# CPU_BOARD.net
KiCad netlist of a schematic drawn in EAGLE
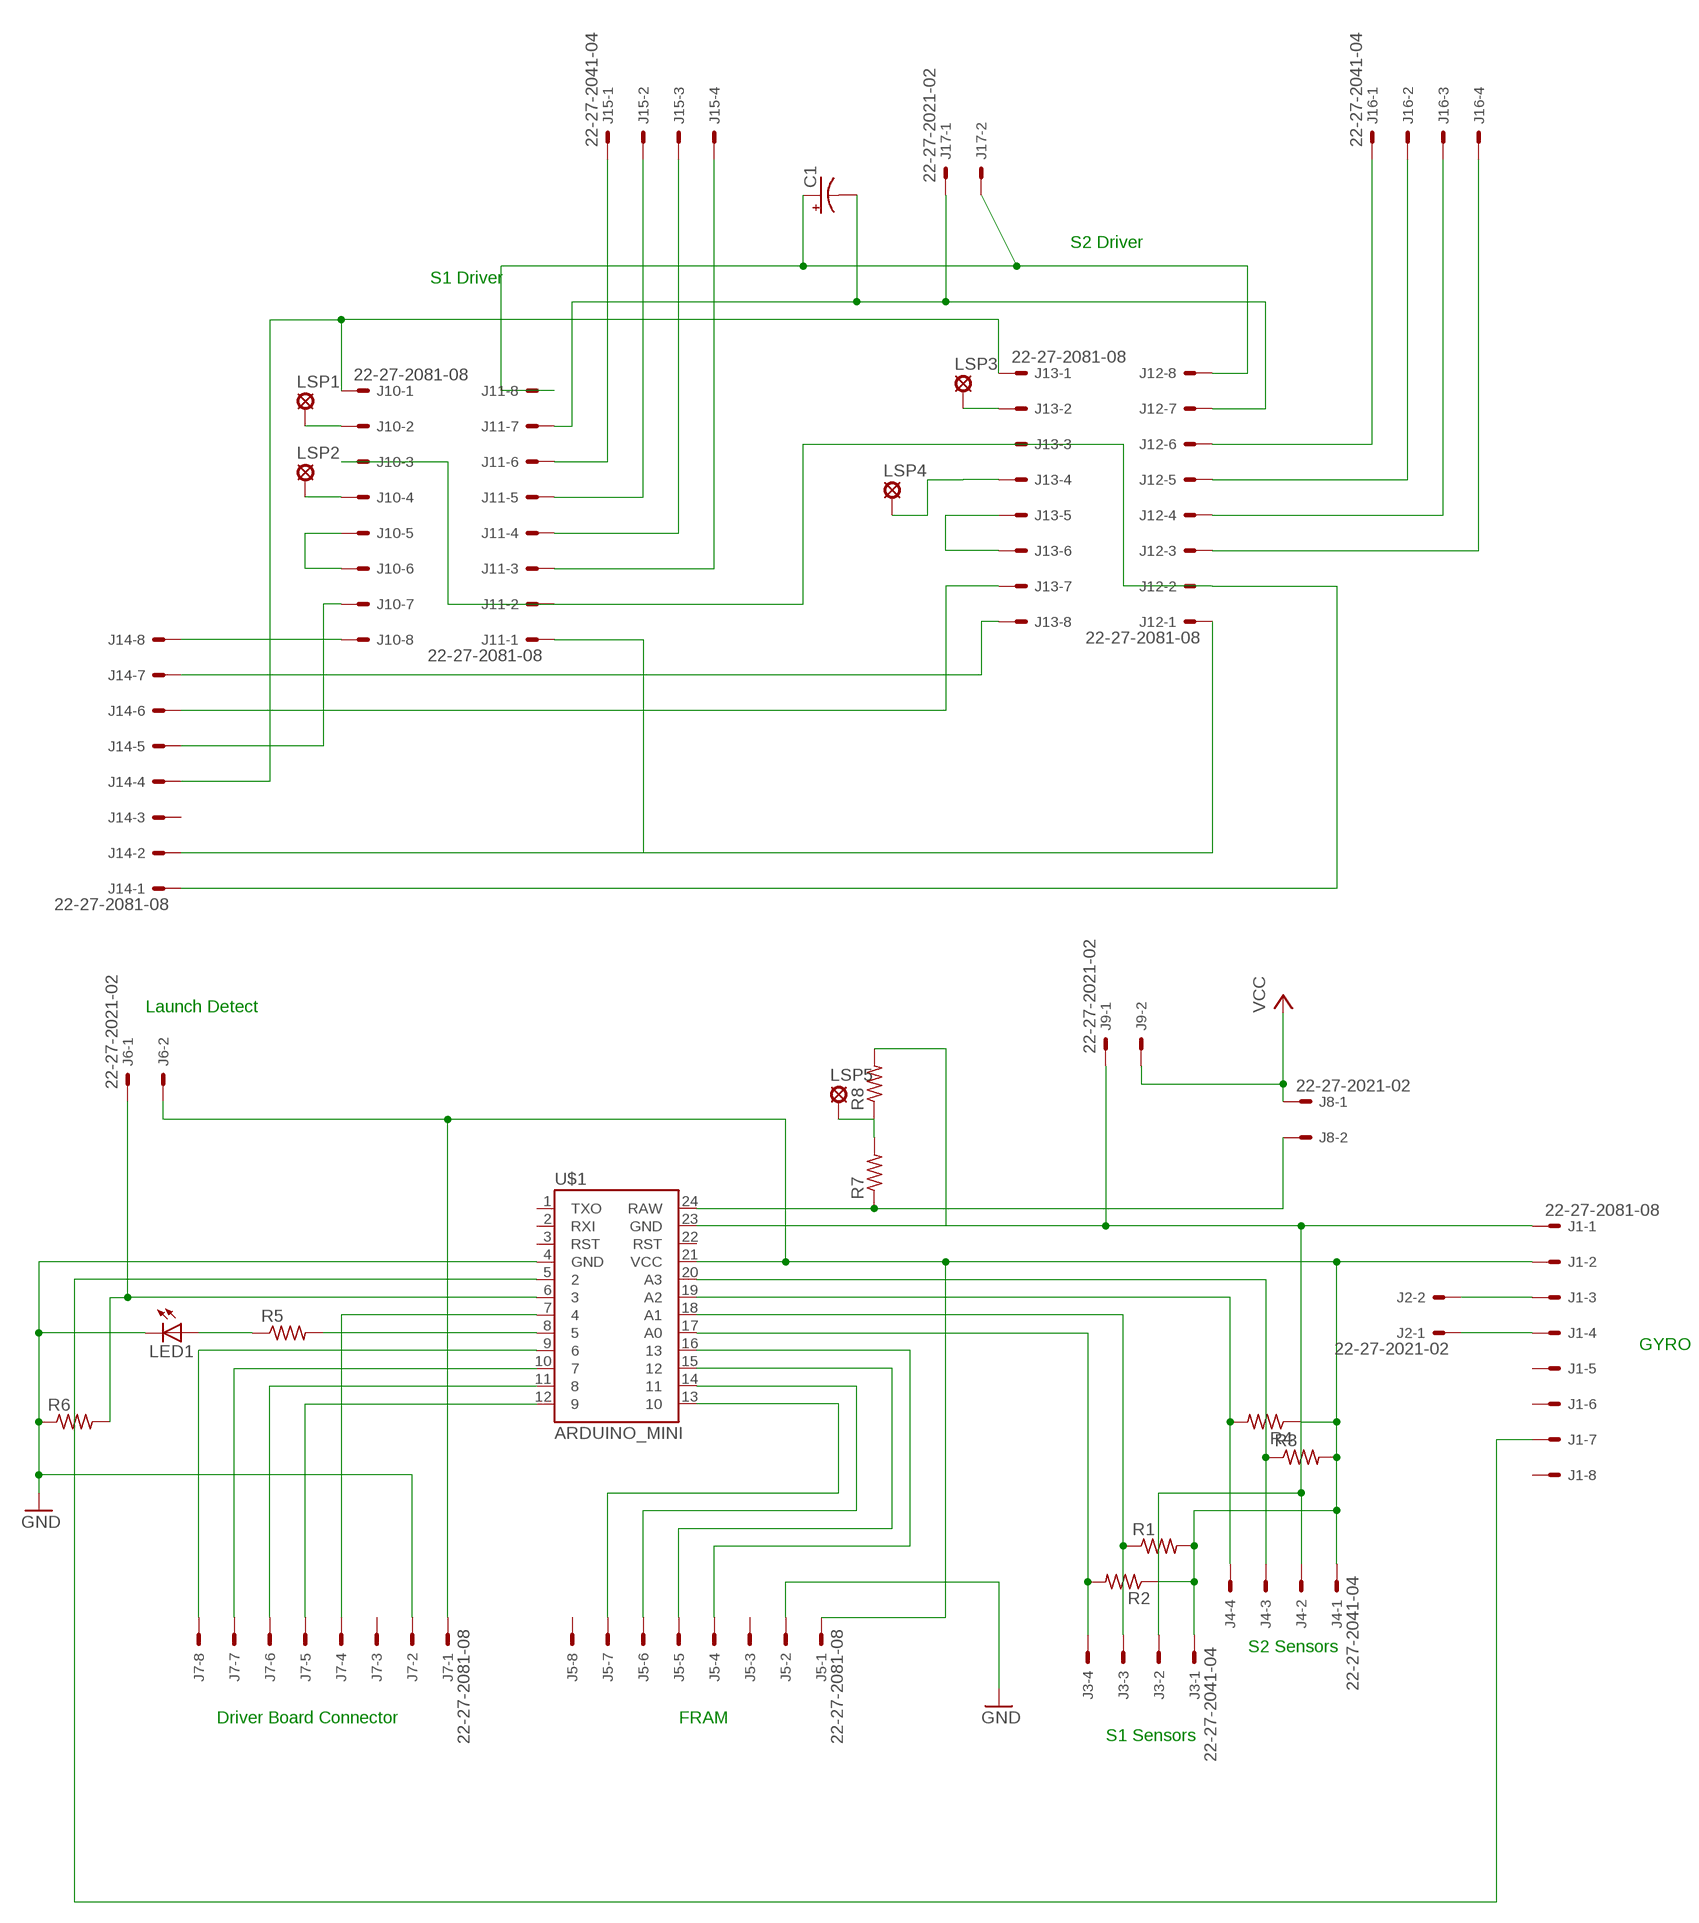
[diagram p0: schematic, sheet 1]

(export (version "E")
  (design (tool "Eeschema 10.0.6"))
  (components
    (comp (ref "C1")
      (value "CPOL-USE2.5-7")
      (footprint "eagle-import:E2,5-7")
      (libsource (lib "eagle-import") (part "CPOL-USE2.5-7"))
    )
    (comp (ref "J1")
      (value "22-27-2081-08")
      (footprint "eagle-import:6410-08")
      (libsource (lib "eagle-import") (part "22-?-0827-2081"))
    )
    (comp (ref "J2")
      (value "22-27-2021-02")
      (footprint "eagle-import:6410-02")
      (libsource (lib "eagle-import") (part "22-?-0227-2021"))
    )
    (comp (ref "J3")
      (value "22-27-2041-04")
      (footprint "eagle-import:6410-04")
      (libsource (lib "eagle-import") (part "22-?-0427-2041"))
    )
    (comp (ref "J4")
      (value "22-27-2041-04")
      (footprint "eagle-import:6410-04")
      (libsource (lib "eagle-import") (part "22-?-0427-2041"))
    )
    (comp (ref "J5")
      (value "22-27-2081-08")
      (footprint "eagle-import:6410-08")
      (libsource (lib "eagle-import") (part "22-?-0827-2081"))
    )
    (comp (ref "J6")
      (value "22-27-2021-02")
      (footprint "eagle-import:6410-02")
      (libsource (lib "eagle-import") (part "22-?-0227-2021"))
    )
    (comp (ref "J7")
      (value "22-27-2081-08")
      (footprint "eagle-import:6410-08")
      (libsource (lib "eagle-import") (part "22-?-0827-2081"))
    )
    (comp (ref "J8")
      (value "22-27-2021-02")
      (footprint "eagle-import:6410-02")
      (libsource (lib "eagle-import") (part "22-?-0227-2021"))
    )
    (comp (ref "J9")
      (value "22-27-2021-02")
      (footprint "eagle-import:6410-02")
      (libsource (lib "eagle-import") (part "22-?-0227-2021"))
    )
    (comp (ref "J10")
      (value "22-27-2081-08")
      (footprint "eagle-import:6410-08")
      (libsource (lib "eagle-import") (part "22-?-0827-2081"))
    )
    (comp (ref "J11")
      (value "22-27-2081-08")
      (footprint "eagle-import:6410-08")
      (libsource (lib "eagle-import") (part "22-?-0827-2081"))
    )
    (comp (ref "J12")
      (value "22-27-2081-08")
      (footprint "eagle-import:6410-08")
      (libsource (lib "eagle-import") (part "22-?-0827-2081"))
    )
    (comp (ref "J13")
      (value "22-27-2081-08")
      (footprint "eagle-import:6410-08")
      (libsource (lib "eagle-import") (part "22-?-0827-2081"))
    )
    (comp (ref "J14")
      (value "22-27-2081-08")
      (footprint "eagle-import:6410-08")
      (libsource (lib "eagle-import") (part "22-?-0827-2081"))
    )
    (comp (ref "J15")
      (value "22-27-2041-04")
      (footprint "eagle-import:6410-04")
      (libsource (lib "eagle-import") (part "22-?-0427-2041"))
    )
    (comp (ref "J16")
      (value "22-27-2041-04")
      (footprint "eagle-import:6410-04")
      (libsource (lib "eagle-import") (part "22-?-0427-2041"))
    )
    (comp (ref "J17")
      (value "22-27-2021-02")
      (footprint "eagle-import:6410-02")
      (libsource (lib "eagle-import") (part "22-?-0227-2021"))
    )
    (comp (ref "LED1")
      (value "LED5MM")
      (footprint "eagle-import:LED5MM")
      (libsource (lib "eagle-import") (part "LED5MM"))
    )
    (comp (ref "LSP1")
      (value "LSP10")
      (footprint "eagle-import:LSP10")
      (libsource (lib "eagle-import") (part "LSP10"))
    )
    (comp (ref "LSP2")
      (value "LSP10")
      (footprint "eagle-import:LSP10")
      (libsource (lib "eagle-import") (part "LSP10"))
    )
    (comp (ref "LSP3")
      (value "LSP10")
      (footprint "eagle-import:LSP10")
      (libsource (lib "eagle-import") (part "LSP10"))
    )
    (comp (ref "LSP4")
      (value "LSP10")
      (footprint "eagle-import:LSP10")
      (libsource (lib "eagle-import") (part "LSP10"))
    )
    (comp (ref "LSP5")
      (value "LSP11")
      (footprint "eagle-import:LSP11")
      (libsource (lib "eagle-import") (part "LSP11"))
    )
    (comp (ref "R1")
      (value "R-US_0204/5")
      (footprint "eagle-import:0204_5")
      (libsource (lib "eagle-import") (part "R-US_0204/5"))
    )
    (comp (ref "R2")
      (value "R-US_0204/5")
      (footprint "eagle-import:0204_5")
      (libsource (lib "eagle-import") (part "R-US_0204/5"))
    )
    (comp (ref "R3")
      (value "R-US_0204/5")
      (footprint "eagle-import:0204_5")
      (libsource (lib "eagle-import") (part "R-US_0204/5"))
    )
    (comp (ref "R4")
      (value "R-US_0204/5")
      (footprint "eagle-import:0204_5")
      (libsource (lib "eagle-import") (part "R-US_0204/5"))
    )
    (comp (ref "R5")
      (value "R-US_0204/5")
      (footprint "eagle-import:0204_5")
      (libsource (lib "eagle-import") (part "resistor_R-US_0204/5"))
    )
    (comp (ref "R6")
      (value "R-US_0204/5")
      (footprint "eagle-import:0204_5")
      (libsource (lib "eagle-import") (part "R-US_0204/5"))
    )
    (comp (ref "R7")
      (value "R-US_0204/5")
      (footprint "eagle-import:0204_5")
      (libsource (lib "eagle-import") (part "R-US_0204/5"))
    )
    (comp (ref "R8")
      (value "R-US_0204/5")
      (footprint "eagle-import:0204_5")
      (libsource (lib "eagle-import") (part "R-US_0204/5"))
    )
    (comp (ref "U$1")
      (value "ARDUINO_MINI")
      (footprint "eagle-import:ARDUINO_MINI")
      (libsource (lib "eagle-import") (part "ARDUINO_MINI"))
    )
  )
  (nets
    (net (code "1") (name "GND") (class "Default")
      (node (ref "J5") (pin "2") (pinfunction "S_2") (pintype "passive"))
      (node (ref "J7") (pin "2") (pinfunction "S_2") (pintype "passive"))
      (node (ref "LED1") (pin "K") (pinfunction "C_K") (pintype "passive"))
      (node (ref "R6") (pin "1") (pinfunction "1_1") (pintype "passive"))
      (node (ref "U$1") (pin "4") (pinfunction "GND_4") (pintype "bidirectional"))
    )
    (net (code "2") (name "Net-(J1A-S)") (class "Default")
      (node (ref "J1") (pin "1") (pinfunction "S_1") (pintype "passive"))
      (node (ref "J3") (pin "2") (pinfunction "S_2") (pintype "passive"))
      (node (ref "J4") (pin "2") (pinfunction "S_2") (pintype "passive"))
      (node (ref "J9") (pin "1") (pinfunction "S_1") (pintype "passive"))
      (node (ref "R8") (pin "2") (pinfunction "2_2") (pintype "passive"))
      (node (ref "U$1") (pin "23") (pinfunction "GND_23") (pintype "bidirectional"))
    )
    (net (code "3") (name "Net-(J1B-S)") (class "Default")
      (node (ref "J1") (pin "2") (pinfunction "S_2") (pintype "passive"))
      (node (ref "J3") (pin "1") (pinfunction "S_1") (pintype "passive"))
      (node (ref "J4") (pin "1") (pinfunction "S_1") (pintype "passive"))
      (node (ref "J5") (pin "1") (pinfunction "S_1") (pintype "passive"))
      (node (ref "J6") (pin "2") (pinfunction "S_2") (pintype "passive"))
      (node (ref "J7") (pin "1") (pinfunction "S_1") (pintype "passive"))
      (node (ref "R1") (pin "2") (pinfunction "2_2") (pintype "passive"))
      (node (ref "R2") (pin "1") (pinfunction "1_1") (pintype "passive"))
      (node (ref "R3") (pin "2") (pinfunction "2_2") (pintype "passive"))
      (node (ref "R4") (pin "1") (pinfunction "1_1") (pintype "passive"))
      (node (ref "U$1") (pin "21") (pinfunction "VCC_21") (pintype "bidirectional"))
    )
    (net (code "4") (name "Net-(J1C-S)") (class "Default")
      (node (ref "J1") (pin "3") (pinfunction "S_3") (pintype "passive"))
      (node (ref "J2") (pin "2") (pinfunction "S_2") (pintype "passive"))
    )
    (net (code "5") (name "Net-(J1D-S)") (class "Default")
      (node (ref "J1") (pin "4") (pinfunction "S_4") (pintype "passive"))
      (node (ref "J2") (pin "1") (pinfunction "S_1") (pintype "passive"))
    )
    (net (code "6") (name "Net-(J1G-S)") (class "Default")
      (node (ref "J1") (pin "7") (pinfunction "S_7") (pintype "passive"))
      (node (ref "U$1") (pin "5") (pinfunction "2_5") (pintype "bidirectional"))
    )
    (net (code "7") (name "Net-(J3C-S)") (class "Default")
      (node (ref "J3") (pin "3") (pinfunction "S_3") (pintype "passive"))
      (node (ref "R1") (pin "1") (pinfunction "1_1") (pintype "passive"))
      (node (ref "U$1") (pin "18") (pinfunction "A1_18") (pintype "bidirectional"))
    )
    (net (code "8") (name "Net-(J3D-S)") (class "Default")
      (node (ref "J3") (pin "4") (pinfunction "S_4") (pintype "passive"))
      (node (ref "R2") (pin "2") (pinfunction "2_2") (pintype "passive"))
      (node (ref "U$1") (pin "17") (pinfunction "A0_17") (pintype "bidirectional"))
    )
    (net (code "9") (name "Net-(J4C-S)") (class "Default")
      (node (ref "J4") (pin "3") (pinfunction "S_3") (pintype "passive"))
      (node (ref "R3") (pin "1") (pinfunction "1_1") (pintype "passive"))
      (node (ref "U$1") (pin "20") (pinfunction "A3_20") (pintype "bidirectional"))
    )
    (net (code "10") (name "Net-(J4D-S)") (class "Default")
      (node (ref "J4") (pin "4") (pinfunction "S_4") (pintype "passive"))
      (node (ref "R4") (pin "2") (pinfunction "2_2") (pintype "passive"))
      (node (ref "U$1") (pin "19") (pinfunction "A2_19") (pintype "bidirectional"))
    )
    (net (code "11") (name "Net-(J5D-S)") (class "Default")
      (node (ref "J5") (pin "4") (pinfunction "S_4") (pintype "passive"))
      (node (ref "U$1") (pin "16") (pinfunction "13_16") (pintype "bidirectional"))
    )
    (net (code "12") (name "Net-(J5E-S)") (class "Default")
      (node (ref "J5") (pin "5") (pinfunction "S_5") (pintype "passive"))
      (node (ref "U$1") (pin "15") (pinfunction "12_15") (pintype "bidirectional"))
    )
    (net (code "13") (name "Net-(J5F-S)") (class "Default")
      (node (ref "J5") (pin "6") (pinfunction "S_6") (pintype "passive"))
      (node (ref "U$1") (pin "14") (pinfunction "11_14") (pintype "bidirectional"))
    )
    (net (code "14") (name "Net-(J5G-S)") (class "Default")
      (node (ref "J5") (pin "7") (pinfunction "S_7") (pintype "passive"))
      (node (ref "U$1") (pin "13") (pinfunction "10_13") (pintype "bidirectional"))
    )
    (net (code "15") (name "Net-(J6A-S)") (class "Default")
      (node (ref "J6") (pin "1") (pinfunction "S_1") (pintype "passive"))
      (node (ref "R6") (pin "2") (pinfunction "2_2") (pintype "passive"))
      (node (ref "U$1") (pin "6") (pinfunction "3_6") (pintype "bidirectional"))
    )
    (net (code "16") (name "Net-(J7D-S)") (class "Default")
      (node (ref "J7") (pin "4") (pinfunction "S_4") (pintype "passive"))
      (node (ref "U$1") (pin "7") (pinfunction "4_7") (pintype "bidirectional"))
    )
    (net (code "17") (name "Net-(J7E-S)") (class "Default")
      (node (ref "J7") (pin "5") (pinfunction "S_5") (pintype "passive"))
      (node (ref "U$1") (pin "12") (pinfunction "9_12") (pintype "bidirectional"))
    )
    (net (code "18") (name "Net-(J7F-S)") (class "Default")
      (node (ref "J7") (pin "6") (pinfunction "S_6") (pintype "passive"))
      (node (ref "U$1") (pin "11") (pinfunction "8_11") (pintype "bidirectional"))
    )
    (net (code "19") (name "Net-(J7G-S)") (class "Default")
      (node (ref "J7") (pin "7") (pinfunction "S_7") (pintype "passive"))
      (node (ref "U$1") (pin "10") (pinfunction "7_10") (pintype "bidirectional"))
    )
    (net (code "20") (name "Net-(J7H-S)") (class "Default")
      (node (ref "J7") (pin "8") (pinfunction "S_8") (pintype "passive"))
      (node (ref "U$1") (pin "9") (pinfunction "6_9") (pintype "bidirectional"))
    )
    (net (code "21") (name "Net-(J8B-S)") (class "Default")
      (node (ref "J8") (pin "2") (pinfunction "S_2") (pintype "passive"))
      (node (ref "R7") (pin "1") (pinfunction "1_1") (pintype "passive"))
      (node (ref "U$1") (pin "24") (pinfunction "RAW_24") (pintype "bidirectional"))
    )
    (net (code "22") (name "Net-(J10A-S)") (class "Default")
      (node (ref "J10") (pin "1") (pinfunction "S_1") (pintype "passive"))
      (node (ref "J13") (pin "1") (pinfunction "S_1") (pintype "passive"))
      (node (ref "J14") (pin "4") (pinfunction "S_4") (pintype "passive"))
    )
    (net (code "23") (name "Net-(J10B-S)") (class "Default")
      (node (ref "J10") (pin "2") (pinfunction "S_2") (pintype "passive"))
      (node (ref "LSP1") (pin "MP") (pinfunction "MP_MP") (pintype "passive"))
    )
    (net (code "24") (name "Net-(J10C-S)") (class "Default")
      (node (ref "J10") (pin "3") (pinfunction "S_3") (pintype "passive"))
      (node (ref "J11") (pin "2") (pinfunction "S_2") (pintype "passive"))
      (node (ref "J12") (pin "2") (pinfunction "S_2") (pintype "passive"))
      (node (ref "J13") (pin "3") (pinfunction "S_3") (pintype "passive"))
      (node (ref "J14") (pin "1") (pinfunction "S_1") (pintype "passive"))
    )
    (net (code "25") (name "Net-(J10D-S)") (class "Default")
      (node (ref "J10") (pin "4") (pinfunction "S_4") (pintype "passive"))
      (node (ref "LSP2") (pin "MP") (pinfunction "MP_MP") (pintype "passive"))
    )
    (net (code "26") (name "Net-(J10E-S)") (class "Default")
      (node (ref "J10") (pin "5") (pinfunction "S_5") (pintype "passive"))
      (node (ref "J10") (pin "6") (pinfunction "S_6") (pintype "passive"))
    )
    (net (code "27") (name "Net-(J10G-S)") (class "Default")
      (node (ref "J10") (pin "7") (pinfunction "S_7") (pintype "passive"))
      (node (ref "J14") (pin "5") (pinfunction "S_5") (pintype "passive"))
    )
    (net (code "28") (name "Net-(J10H-S)") (class "Default")
      (node (ref "J10") (pin "8") (pinfunction "S_8") (pintype "passive"))
      (node (ref "J14") (pin "8") (pinfunction "S_8") (pintype "passive"))
    )
    (net (code "29") (name "Net-(J11A-S)") (class "Default")
      (node (ref "J11") (pin "1") (pinfunction "S_1") (pintype "passive"))
      (node (ref "J12") (pin "1") (pinfunction "S_1") (pintype "passive"))
      (node (ref "J14") (pin "2") (pinfunction "S_2") (pintype "passive"))
    )
    (net (code "30") (name "Net-(J11C-S)") (class "Default")
      (node (ref "J11") (pin "3") (pinfunction "S_3") (pintype "passive"))
      (node (ref "J15") (pin "4") (pinfunction "S_4") (pintype "passive"))
    )
    (net (code "31") (name "Net-(J11D-S)") (class "Default")
      (node (ref "J11") (pin "4") (pinfunction "S_4") (pintype "passive"))
      (node (ref "J15") (pin "3") (pinfunction "S_3") (pintype "passive"))
    )
    (net (code "32") (name "Net-(J11E-S)") (class "Default")
      (node (ref "J11") (pin "5") (pinfunction "S_5") (pintype "passive"))
      (node (ref "J15") (pin "2") (pinfunction "S_2") (pintype "passive"))
    )
    (net (code "33") (name "Net-(J11F-S)") (class "Default")
      (node (ref "J11") (pin "6") (pinfunction "S_6") (pintype "passive"))
      (node (ref "J15") (pin "1") (pinfunction "S_1") (pintype "passive"))
    )
    (net (code "34") (name "Net-(J11G-S)") (class "Default")
      (node (ref "C1") (pin "-") (pinfunction "-_-") (pintype "passive"))
      (node (ref "J11") (pin "7") (pinfunction "S_7") (pintype "passive"))
      (node (ref "J12") (pin "7") (pinfunction "S_7") (pintype "passive"))
      (node (ref "J17") (pin "1") (pinfunction "S_1") (pintype "passive"))
    )
    (net (code "35") (name "Net-(J11H-S)") (class "Default")
      (node (ref "C1") (pin "+") (pinfunction "+_+") (pintype "passive"))
      (node (ref "J11") (pin "8") (pinfunction "S_8") (pintype "passive"))
      (node (ref "J12") (pin "8") (pinfunction "S_8") (pintype "passive"))
      (node (ref "J17") (pin "2") (pinfunction "S_2") (pintype "passive"))
    )
    (net (code "36") (name "Net-(J12C-S)") (class "Default")
      (node (ref "J12") (pin "3") (pinfunction "S_3") (pintype "passive"))
      (node (ref "J16") (pin "4") (pinfunction "S_4") (pintype "passive"))
    )
    (net (code "37") (name "Net-(J12D-S)") (class "Default")
      (node (ref "J12") (pin "4") (pinfunction "S_4") (pintype "passive"))
      (node (ref "J16") (pin "3") (pinfunction "S_3") (pintype "passive"))
    )
    (net (code "38") (name "Net-(J12E-S)") (class "Default")
      (node (ref "J12") (pin "5") (pinfunction "S_5") (pintype "passive"))
      (node (ref "J16") (pin "2") (pinfunction "S_2") (pintype "passive"))
    )
    (net (code "39") (name "Net-(J12F-S)") (class "Default")
      (node (ref "J12") (pin "6") (pinfunction "S_6") (pintype "passive"))
      (node (ref "J16") (pin "1") (pinfunction "S_1") (pintype "passive"))
    )
    (net (code "40") (name "Net-(J13B-S)") (class "Default")
      (node (ref "J13") (pin "2") (pinfunction "S_2") (pintype "passive"))
      (node (ref "LSP3") (pin "MP") (pinfunction "MP_MP") (pintype "passive"))
    )
    (net (code "41") (name "Net-(J13D-S)") (class "Default")
      (node (ref "J13") (pin "4") (pinfunction "S_4") (pintype "passive"))
      (node (ref "LSP4") (pin "MP") (pinfunction "MP_MP") (pintype "passive"))
    )
    (net (code "42") (name "Net-(J13E-S)") (class "Default")
      (node (ref "J13") (pin "5") (pinfunction "S_5") (pintype "passive"))
      (node (ref "J13") (pin "6") (pinfunction "S_6") (pintype "passive"))
    )
    (net (code "43") (name "Net-(J13G-S)") (class "Default")
      (node (ref "J13") (pin "7") (pinfunction "S_7") (pintype "passive"))
      (node (ref "J14") (pin "6") (pinfunction "S_6") (pintype "passive"))
    )
    (net (code "44") (name "Net-(J13H-S)") (class "Default")
      (node (ref "J13") (pin "8") (pinfunction "S_8") (pintype "passive"))
      (node (ref "J14") (pin "7") (pinfunction "S_7") (pintype "passive"))
    )
    (net (code "45") (name "Net-(LED1-PadA)") (class "Default")
      (node (ref "LED1") (pin "A") (pinfunction "A_A") (pintype "passive"))
      (node (ref "R5") (pin "1") (pinfunction "1_1") (pintype "passive"))
    )
    (net (code "46") (name "Net-(LSP5-PadMP)") (class "Default")
      (node (ref "LSP5") (pin "MP") (pinfunction "MP_MP") (pintype "passive"))
      (node (ref "R7") (pin "2") (pinfunction "2_2") (pintype "passive"))
      (node (ref "R8") (pin "1") (pinfunction "1_1") (pintype "passive"))
    )
    (net (code "47") (name "Net-(U$1-5)") (class "Default")
      (node (ref "R5") (pin "2") (pinfunction "2_2") (pintype "passive"))
      (node (ref "U$1") (pin "8") (pinfunction "5_8") (pintype "bidirectional"))
    )
    (net (code "48") (name "VCC") (class "Default")
      (node (ref "J8") (pin "1") (pinfunction "S_1") (pintype "passive"))
      (node (ref "J9") (pin "2") (pinfunction "S_2") (pintype "passive"))
    )
    (net (code "49") (name "unconnected-(J1E-S-Pad5)") (class "Default")
      (node (ref "J1") (pin "5") (pinfunction "S_5") (pintype "passive"))
    )
    (net (code "50") (name "unconnected-(J1F-S-Pad6)") (class "Default")
      (node (ref "J1") (pin "6") (pinfunction "S_6") (pintype "passive"))
    )
    (net (code "51") (name "unconnected-(J1H-S-Pad8)") (class "Default")
      (node (ref "J1") (pin "8") (pinfunction "S_8") (pintype "passive"))
    )
    (net (code "52") (name "unconnected-(J5C-S-Pad3)") (class "Default")
      (node (ref "J5") (pin "3") (pinfunction "S_3") (pintype "passive"))
    )
    (net (code "53") (name "unconnected-(J5H-S-Pad8)") (class "Default")
      (node (ref "J5") (pin "8") (pinfunction "S_8") (pintype "passive"))
    )
    (net (code "54") (name "unconnected-(J7C-S-Pad3)") (class "Default")
      (node (ref "J7") (pin "3") (pinfunction "S_3") (pintype "passive"))
    )
    (net (code "55") (name "unconnected-(J14C-S-Pad3)") (class "Default")
      (node (ref "J14") (pin "3") (pinfunction "S_3") (pintype "passive"))
    )
    (net (code "56") (name "unconnected-(U$1-RST-Pad3)") (class "Default")
      (node (ref "U$1") (pin "3") (pinfunction "RST_3") (pintype "bidirectional"))
    )
    (net (code "57") (name "unconnected-(U$1-RST-Pad22)") (class "Default")
      (node (ref "U$1") (pin "22") (pinfunction "RST_22") (pintype "bidirectional"))
    )
    (net (code "58") (name "unconnected-(U$1-RXI-Pad2)") (class "Default")
      (node (ref "U$1") (pin "2") (pinfunction "RXI_2") (pintype "bidirectional"))
    )
    (net (code "59") (name "unconnected-(U$1-TXO-Pad1)") (class "Default")
      (node (ref "U$1") (pin "1") (pinfunction "TXO_1") (pintype "bidirectional"))
    )
  )
)
